# ALERT.net
KiCad netlist of a schematic drawn in Altium Designer
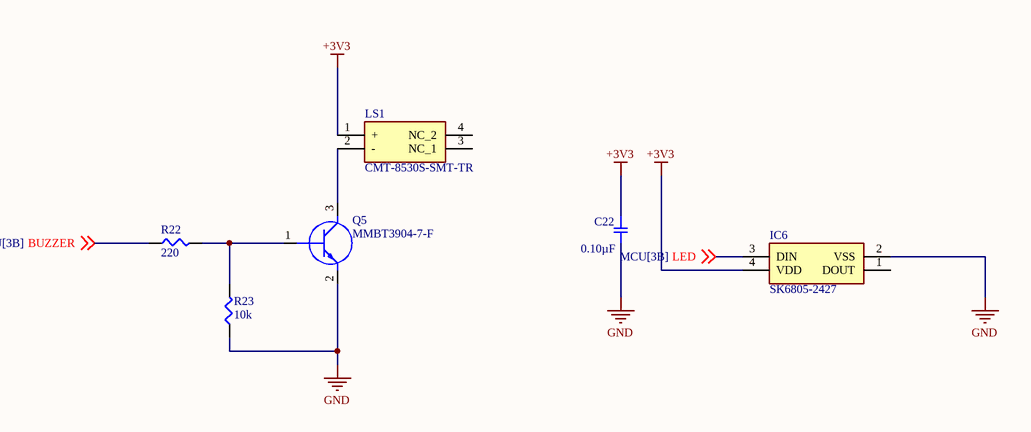
[diagram p0: ALERT.SchDoc]

(export (version "E")
  (design (tool "Eeschema 10.0.6"))
  (components
    (comp (ref "C22")
      (value "0.10µF")
      (footprint "SMD-0402C")
      (description "CAP CER 0.1UF 16V X7R 0402")
      (fields
        (field (name "DIGI-KEY PART NUMBER") "490-4759-1-ND")
        (field (name "PART NUMBER") "GCM155R71C104KA55D")
      )
      (libsource (lib "capacitor_murata_0402") (part "GCM155R71C104KA55D"))
    )
    (comp (ref "IC6")
      (value "SK6805-2427")
      (footprint "SamacSys:SK68052427")
      (description "Integrated Circuit")
      (libsource (lib "SamacSys") (part "SK6805-2427"))
    )
    (comp (ref "LS1")
      (value "CMT-8530S-SMT-TR")
      (footprint "SamacSys:CMT8530SSMTTR")
      (description "Loudspeaker or Buzzer")
      (fields (field (name "MOUSER PART NUMBER") "490-CMT-8530S-SMT-TR"))
      (libsource (lib "SamacSys") (part "CMT-8530S-SMT-TR"))
    )
    (comp (ref "Q5")
      (value "MMBT3904-7-F")
      (footprint "SamacSys:SOT96P240X110-3N")
      (description "Transistor BJT NPN")
      (fields (field (name "MOUSER PART NUMBER") "621-MMBT3904-F"))
      (libsource (lib "*") (part "MMBT3904-7-F"))
    )
    (comp (ref "R22")
      (value "220")
      (footprint "SMD-0402-RES")
      (description "RES SMD 220 OHM 1% 1/10W 0402")
      (fields (field (name "PART NUMBER") "ERJ-2RKF2200X") (field (name "DIGI-KEY PART NUMBER") "P220LCT-ND"))
      (libsource (lib "Panasonic_ERJ_0402") (part "ERJ-2RKF2200X"))
    )
    (comp (ref "R23")
      (value "10k")
      (footprint "SMD-0402-RES")
      (description "RES SMD 10K OHM 5% 1/10W 0402")
      (fields (field (name "PART NUMBER") "ERJ-2GEJ103X") (field (name "DIGI-KEY PART NUMBER") "P10KJCT-ND"))
      (libsource (lib "Panasonic_ERJ_0402") (part "ERJ-2GEJ103X"))
    )
  )
  (nets
    (net (code "1") (name "+3V3") (class "Default")
      (node (ref "C22") (pin "1") (pinfunction "1_1") (pintype "passive"))
      (node (ref "IC6") (pin "4") (pinfunction "VDD_4") (pintype "passive"))
      (node (ref "LS1") (pin "1") (pinfunction "+_1") (pintype "passive"))
    )
    (net (code "2") (name "BUZZER") (class "Default")
      (node (ref "R22") (pin "1") (pinfunction "1_1") (pintype "passive"))
    )
    (net (code "3") (name "GND") (class "Default")
      (node (ref "C22") (pin "2") (pinfunction "2_2") (pintype "passive"))
      (node (ref "IC6") (pin "2") (pinfunction "VSS_2") (pintype "passive"))
      (node (ref "Q5") (pin "2") (pinfunction "E_2") (pintype "passive"))
      (node (ref "R23") (pin "1") (pinfunction "1_1") (pintype "passive"))
    )
    (net (code "4") (name "LED") (class "Default")
      (node (ref "IC6") (pin "3") (pinfunction "DIN_3") (pintype "passive"))
    )
    (net (code "5") (name "Net-(LS1--)") (class "Default")
      (node (ref "LS1") (pin "2") (pinfunction "-_2") (pintype "passive"))
      (node (ref "Q5") (pin "3") (pinfunction "C_3") (pintype "passive"))
    )
    (net (code "6") (name "Net-(Q5-B)") (class "Default")
      (node (ref "Q5") (pin "1") (pinfunction "B_1") (pintype "passive"))
      (node (ref "R22") (pin "2") (pinfunction "2_2") (pintype "passive"))
      (node (ref "R23") (pin "2") (pinfunction "2_2") (pintype "passive"))
    )
    (net (code "7") (name "unconnected-(IC6-DOUT-Pad1)") (class "Default")
      (node (ref "IC6") (pin "1") (pinfunction "DOUT_1") (pintype "passive"))
    )
    (net (code "8") (name "unconnected-(LS1-NC_1-Pad3)") (class "Default")
      (node (ref "LS1") (pin "3") (pinfunction "NC_1_3") (pintype "passive"))
    )
    (net (code "9") (name "unconnected-(LS1-NC_2-Pad4)") (class "Default")
      (node (ref "LS1") (pin "4") (pinfunction "NC_2_4") (pintype "passive"))
    )
  )
)
